# RFMDisplay.net
KiCad netlist of a schematic drawn in EAGLE
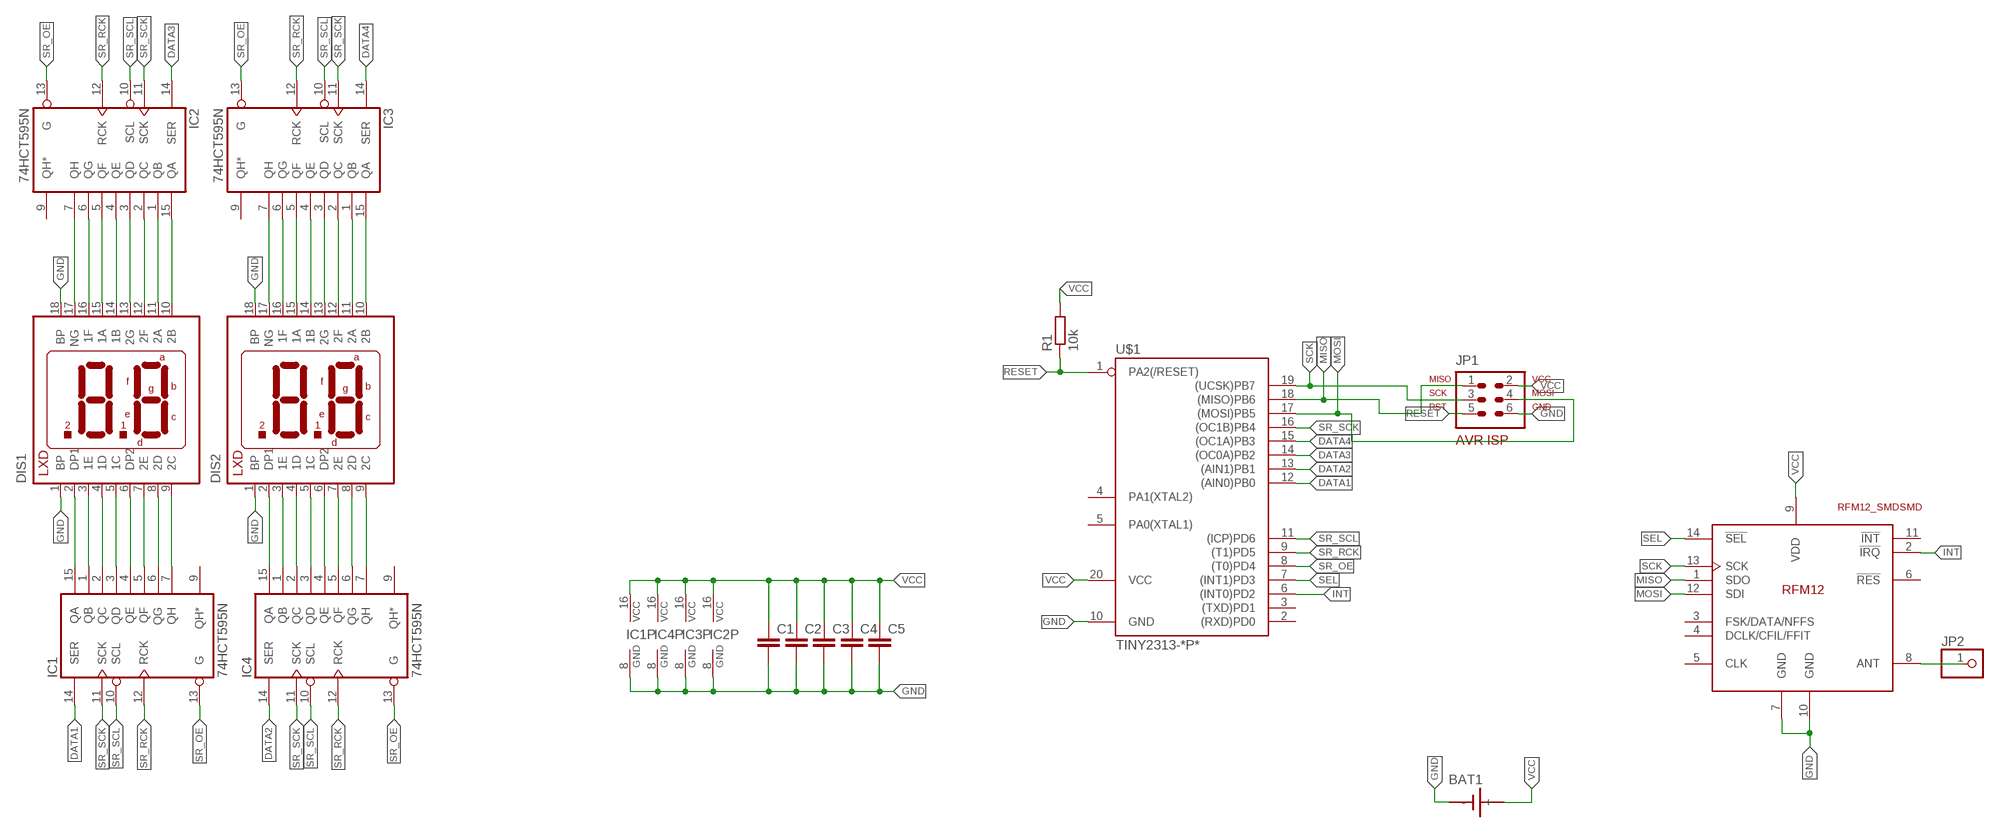
[diagram p0: schematic, sheet 1]

(export (version "E")
  (design (tool "Eeschema 10.0.6"))
  (components
    (comp (ref "BAT1")
      (value "SN2032")
      (footprint "eagle-import:SN2032")
      (libsource (lib "eagle-import") (part "SN2032"))
    )
    (comp (ref "C1")
      (value "C-EUC0805")
      (footprint "eagle-import:C0805")
      (libsource (lib "eagle-import") (part "C-EUC0805"))
    )
    (comp (ref "C2")
      (value "C-EUC0805")
      (footprint "eagle-import:C0805")
      (libsource (lib "eagle-import") (part "C-EUC0805"))
    )
    (comp (ref "C3")
      (value "C-EUC0805")
      (footprint "eagle-import:C0805")
      (libsource (lib "eagle-import") (part "C-EUC0805"))
    )
    (comp (ref "C4")
      (value "C-EUC0805")
      (footprint "eagle-import:C0805")
      (libsource (lib "eagle-import") (part "C-EUC0805"))
    )
    (comp (ref "C5")
      (value "C-EUC0805")
      (footprint "eagle-import:C0805")
      (libsource (lib "eagle-import") (part "C-EUC0805"))
    )
    (comp (ref "DIS1")
      (value "29DIP")
      (footprint "eagle-import:29-D")
      (libsource (lib "eagle-import") (part "29DIP"))
    )
    (comp (ref "DIS2")
      (value "29DIP")
      (footprint "eagle-import:29-D")
      (libsource (lib "eagle-import") (part "29DIP"))
    )
    (comp (ref "IC1")
      (value "74HCT595N")
      (footprint "eagle-import:DIL16")
      (libsource (lib "eagle-import") (part "74595NHCT"))
    )
    (comp (ref "IC2")
      (value "74HCT595N")
      (footprint "eagle-import:DIL16")
      (libsource (lib "eagle-import") (part "74595NHCT"))
    )
    (comp (ref "IC3")
      (value "74HCT595N")
      (footprint "eagle-import:DIL16")
      (libsource (lib "eagle-import") (part "74595NHCT"))
    )
    (comp (ref "IC4")
      (value "74HCT595N")
      (footprint "eagle-import:DIL16")
      (libsource (lib "eagle-import") (part "74595NHCT"))
    )
    (comp (ref "JP1")
      (value "AVR-ISP-6VERT")
      (footprint "eagle-import:AVR-ISP-6")
      (libsource (lib "eagle-import") (part "AVR-ISP-6VERT"))
    )
    (comp (ref "JP2")
      (value "PINHD-1X1")
      (footprint "eagle-import:1X01")
      (libsource (lib "eagle-import") (part "PINHD-1X1"))
    )
    (comp (ref "R1")
      (value "10k")
      (footprint "eagle-import:R1206")
      (libsource (lib "eagle-import") (part "R-EU_R1206"))
    )
    (comp (ref "U$1")
      (value "TINY2313-*P*")
      (footprint "eagle-import:DIL20")
      (libsource (lib "eagle-import") (part "TINY2313-P"))
    )
    (comp (ref "U$2")
      (value "RFM12_SMDSMD")
      (footprint "eagle-import:RFM12")
      (libsource (lib "eagle-import") (part "RFM12_SMDSMD"))
    )
  )
  (nets
    (net (code "1") (name "DATA1") (class "Default")
      (node (ref "IC1") (pin "14") (pinfunction "SER_14") (pintype "input"))
      (node (ref "U$1") (pin "12") (pinfunction "(AIN0)PB0_12") (pintype "bidirectional"))
    )
    (net (code "2") (name "DATA2") (class "Default")
      (node (ref "IC4") (pin "14") (pinfunction "SER_14") (pintype "input"))
      (node (ref "U$1") (pin "13") (pinfunction "(AIN1)PB1_13") (pintype "bidirectional"))
    )
    (net (code "3") (name "DATA3") (class "Default")
      (node (ref "IC2") (pin "14") (pinfunction "SER_14") (pintype "input"))
      (node (ref "U$1") (pin "14") (pinfunction "(OC0A)PB2_14") (pintype "bidirectional"))
    )
    (net (code "4") (name "DATA4") (class "Default")
      (node (ref "IC3") (pin "14") (pinfunction "SER_14") (pintype "input"))
      (node (ref "U$1") (pin "15") (pinfunction "(OC1A)PB3_15") (pintype "bidirectional"))
    )
    (net (code "5") (name "GND") (class "Default")
      (node (ref "BAT1") (pin "-") (pinfunction "-_-") (pintype "passive"))
      (node (ref "C1") (pin "2") (pinfunction "2_2") (pintype "passive"))
      (node (ref "C2") (pin "2") (pinfunction "2_2") (pintype "passive"))
      (node (ref "C3") (pin "2") (pinfunction "2_2") (pintype "passive"))
      (node (ref "C4") (pin "2") (pinfunction "2_2") (pintype "passive"))
      (node (ref "C5") (pin "2") (pinfunction "2_2") (pintype "passive"))
      (node (ref "DIS1") (pin "1") (pinfunction "BP_1") (pintype "passive"))
      (node (ref "DIS1") (pin "18") (pinfunction "BP_18") (pintype "passive"))
      (node (ref "DIS2") (pin "1") (pinfunction "BP_1") (pintype "passive"))
      (node (ref "DIS2") (pin "18") (pinfunction "BP_18") (pintype "passive"))
      (node (ref "IC1") (pin "8") (pinfunction "GND_8") (pintype "power_in"))
      (node (ref "IC2") (pin "8") (pinfunction "GND_8") (pintype "power_in"))
      (node (ref "IC3") (pin "8") (pinfunction "GND_8") (pintype "power_in"))
      (node (ref "IC4") (pin "8") (pinfunction "GND_8") (pintype "power_in"))
      (node (ref "JP1") (pin "6") (pinfunction "6_6") (pintype "passive"))
      (node (ref "U$1") (pin "10") (pinfunction "GND_10") (pintype "power_in"))
      (node (ref "U$2") (pin "10") (pinfunction "GND_10") (pintype "passive"))
      (node (ref "U$2") (pin "7") (pinfunction "GND_7") (pintype "passive"))
    )
    (net (code "6") (name "INT") (class "Default")
      (node (ref "U$1") (pin "6") (pinfunction "(INT0)PD2_6") (pintype "bidirectional"))
      (node (ref "U$2") (pin "2") (pinfunction "~{IRQ}_2") (pintype "output"))
    )
    (net (code "7") (name "MISO") (class "Default")
      (node (ref "JP1") (pin "1") (pinfunction "1_1") (pintype "passive"))
      (node (ref "U$1") (pin "18") (pinfunction "(MISO)PB6_18") (pintype "bidirectional"))
      (node (ref "U$2") (pin "1") (pinfunction "SDO_1") (pintype "output"))
    )
    (net (code "8") (name "MOSI") (class "Default")
      (node (ref "JP1") (pin "4") (pinfunction "4_4") (pintype "passive"))
      (node (ref "U$1") (pin "17") (pinfunction "(MOSI)PB5_17") (pintype "bidirectional"))
      (node (ref "U$2") (pin "12") (pinfunction "SDI_12") (pintype "input"))
    )
    (net (code "9") (name "Net-(DIS1-1A)") (class "Default")
      (node (ref "DIS1") (pin "15") (pinfunction "1A_15") (pintype "passive"))
      (node (ref "IC2") (pin "5") (pinfunction "QF_5") (pintype "tri_state"))
    )
    (net (code "10") (name "Net-(DIS1-1B)") (class "Default")
      (node (ref "DIS1") (pin "14") (pinfunction "1B_14") (pintype "passive"))
      (node (ref "IC2") (pin "4") (pinfunction "QE_4") (pintype "tri_state"))
    )
    (net (code "11") (name "Net-(DIS1-1C)") (class "Default")
      (node (ref "DIS1") (pin "5") (pinfunction "1C_5") (pintype "passive"))
      (node (ref "IC1") (pin "3") (pinfunction "QD_3") (pintype "tri_state"))
    )
    (net (code "12") (name "Net-(DIS1-1D)") (class "Default")
      (node (ref "DIS1") (pin "4") (pinfunction "1D_4") (pintype "passive"))
      (node (ref "IC1") (pin "2") (pinfunction "QC_2") (pintype "tri_state"))
    )
    (net (code "13") (name "Net-(DIS1-1E)") (class "Default")
      (node (ref "DIS1") (pin "3") (pinfunction "1E_3") (pintype "passive"))
      (node (ref "IC1") (pin "1") (pinfunction "QB_1") (pintype "tri_state"))
    )
    (net (code "14") (name "Net-(DIS1-1F)") (class "Default")
      (node (ref "DIS1") (pin "16") (pinfunction "1F_16") (pintype "passive"))
      (node (ref "IC2") (pin "6") (pinfunction "QG_6") (pintype "tri_state"))
    )
    (net (code "15") (name "Net-(DIS1-2A)") (class "Default")
      (node (ref "DIS1") (pin "11") (pinfunction "2A_11") (pintype "passive"))
      (node (ref "IC2") (pin "1") (pinfunction "QB_1") (pintype "tri_state"))
    )
    (net (code "16") (name "Net-(DIS1-2B)") (class "Default")
      (node (ref "DIS1") (pin "10") (pinfunction "2B_10") (pintype "passive"))
      (node (ref "IC2") (pin "15") (pinfunction "QA_15") (pintype "tri_state"))
    )
    (net (code "17") (name "Net-(DIS1-2C)") (class "Default")
      (node (ref "DIS1") (pin "9") (pinfunction "2C_9") (pintype "passive"))
      (node (ref "IC1") (pin "7") (pinfunction "QH_7") (pintype "tri_state"))
    )
    (net (code "18") (name "Net-(DIS1-2D)") (class "Default")
      (node (ref "DIS1") (pin "8") (pinfunction "2D_8") (pintype "passive"))
      (node (ref "IC1") (pin "6") (pinfunction "QG_6") (pintype "tri_state"))
    )
    (net (code "19") (name "Net-(DIS1-2E)") (class "Default")
      (node (ref "DIS1") (pin "7") (pinfunction "2E_7") (pintype "passive"))
      (node (ref "IC1") (pin "5") (pinfunction "QF_5") (pintype "tri_state"))
    )
    (net (code "20") (name "Net-(DIS1-2F)") (class "Default")
      (node (ref "DIS1") (pin "12") (pinfunction "2F_12") (pintype "passive"))
      (node (ref "IC2") (pin "2") (pinfunction "QC_2") (pintype "tri_state"))
    )
    (net (code "21") (name "Net-(DIS1-2G)") (class "Default")
      (node (ref "DIS1") (pin "13") (pinfunction "2G_13") (pintype "passive"))
      (node (ref "IC2") (pin "3") (pinfunction "QD_3") (pintype "tri_state"))
    )
    (net (code "22") (name "Net-(DIS1-DP1)") (class "Default")
      (node (ref "DIS1") (pin "2") (pinfunction "DP1_2") (pintype "passive"))
      (node (ref "IC1") (pin "15") (pinfunction "QA_15") (pintype "tri_state"))
    )
    (net (code "23") (name "Net-(DIS1-DP2)") (class "Default")
      (node (ref "DIS1") (pin "6") (pinfunction "DP2_6") (pintype "passive"))
      (node (ref "IC1") (pin "4") (pinfunction "QE_4") (pintype "tri_state"))
    )
    (net (code "24") (name "Net-(DIS1-NG)") (class "Default")
      (node (ref "DIS1") (pin "17") (pinfunction "NG_17") (pintype "passive"))
      (node (ref "IC2") (pin "7") (pinfunction "QH_7") (pintype "tri_state"))
    )
    (net (code "25") (name "Net-(DIS2-1A)") (class "Default")
      (node (ref "DIS2") (pin "15") (pinfunction "1A_15") (pintype "passive"))
      (node (ref "IC3") (pin "5") (pinfunction "QF_5") (pintype "tri_state"))
    )
    (net (code "26") (name "Net-(DIS2-1B)") (class "Default")
      (node (ref "DIS2") (pin "14") (pinfunction "1B_14") (pintype "passive"))
      (node (ref "IC3") (pin "4") (pinfunction "QE_4") (pintype "tri_state"))
    )
    (net (code "27") (name "Net-(DIS2-1C)") (class "Default")
      (node (ref "DIS2") (pin "5") (pinfunction "1C_5") (pintype "passive"))
      (node (ref "IC4") (pin "3") (pinfunction "QD_3") (pintype "tri_state"))
    )
    (net (code "28") (name "Net-(DIS2-1D)") (class "Default")
      (node (ref "DIS2") (pin "4") (pinfunction "1D_4") (pintype "passive"))
      (node (ref "IC4") (pin "2") (pinfunction "QC_2") (pintype "tri_state"))
    )
    (net (code "29") (name "Net-(DIS2-1E)") (class "Default")
      (node (ref "DIS2") (pin "3") (pinfunction "1E_3") (pintype "passive"))
      (node (ref "IC4") (pin "1") (pinfunction "QB_1") (pintype "tri_state"))
    )
    (net (code "30") (name "Net-(DIS2-1F)") (class "Default")
      (node (ref "DIS2") (pin "16") (pinfunction "1F_16") (pintype "passive"))
      (node (ref "IC3") (pin "6") (pinfunction "QG_6") (pintype "tri_state"))
    )
    (net (code "31") (name "Net-(DIS2-2A)") (class "Default")
      (node (ref "DIS2") (pin "11") (pinfunction "2A_11") (pintype "passive"))
      (node (ref "IC3") (pin "1") (pinfunction "QB_1") (pintype "tri_state"))
    )
    (net (code "32") (name "Net-(DIS2-2B)") (class "Default")
      (node (ref "DIS2") (pin "10") (pinfunction "2B_10") (pintype "passive"))
      (node (ref "IC3") (pin "15") (pinfunction "QA_15") (pintype "tri_state"))
    )
    (net (code "33") (name "Net-(DIS2-2C)") (class "Default")
      (node (ref "DIS2") (pin "9") (pinfunction "2C_9") (pintype "passive"))
      (node (ref "IC4") (pin "7") (pinfunction "QH_7") (pintype "tri_state"))
    )
    (net (code "34") (name "Net-(DIS2-2D)") (class "Default")
      (node (ref "DIS2") (pin "8") (pinfunction "2D_8") (pintype "passive"))
      (node (ref "IC4") (pin "6") (pinfunction "QG_6") (pintype "tri_state"))
    )
    (net (code "35") (name "Net-(DIS2-2E)") (class "Default")
      (node (ref "DIS2") (pin "7") (pinfunction "2E_7") (pintype "passive"))
      (node (ref "IC4") (pin "5") (pinfunction "QF_5") (pintype "tri_state"))
    )
    (net (code "36") (name "Net-(DIS2-2F)") (class "Default")
      (node (ref "DIS2") (pin "12") (pinfunction "2F_12") (pintype "passive"))
      (node (ref "IC3") (pin "2") (pinfunction "QC_2") (pintype "tri_state"))
    )
    (net (code "37") (name "Net-(DIS2-2G)") (class "Default")
      (node (ref "DIS2") (pin "13") (pinfunction "2G_13") (pintype "passive"))
      (node (ref "IC3") (pin "3") (pinfunction "QD_3") (pintype "tri_state"))
    )
    (net (code "38") (name "Net-(DIS2-DP1)") (class "Default")
      (node (ref "DIS2") (pin "2") (pinfunction "DP1_2") (pintype "passive"))
      (node (ref "IC4") (pin "15") (pinfunction "QA_15") (pintype "tri_state"))
    )
    (net (code "39") (name "Net-(DIS2-DP2)") (class "Default")
      (node (ref "DIS2") (pin "6") (pinfunction "DP2_6") (pintype "passive"))
      (node (ref "IC4") (pin "4") (pinfunction "QE_4") (pintype "tri_state"))
    )
    (net (code "40") (name "Net-(DIS2-NG)") (class "Default")
      (node (ref "DIS2") (pin "17") (pinfunction "NG_17") (pintype "passive"))
      (node (ref "IC3") (pin "7") (pinfunction "QH_7") (pintype "tri_state"))
    )
    (net (code "41") (name "Net-(U$2-ANT)") (class "Default")
      (node (ref "JP2") (pin "1") (pinfunction "1_1") (pintype "passive"))
      (node (ref "U$2") (pin "8") (pinfunction "ANT_8") (pintype "bidirectional"))
    )
    (net (code "42") (name "RESET") (class "Default")
      (node (ref "JP1") (pin "5") (pinfunction "5_5") (pintype "passive"))
      (node (ref "R1") (pin "1") (pinfunction "1_1") (pintype "passive"))
      (node (ref "U$1") (pin "1") (pinfunction "PA2(/RESET)_1") (pintype "input"))
    )
    (net (code "43") (name "SCK") (class "Default")
      (node (ref "JP1") (pin "3") (pinfunction "3_3") (pintype "passive"))
      (node (ref "U$1") (pin "19") (pinfunction "(UCSK)PB7_19") (pintype "bidirectional"))
      (node (ref "U$2") (pin "13") (pinfunction "SCK_13") (pintype "input"))
    )
    (net (code "44") (name "SEL") (class "Default")
      (node (ref "U$1") (pin "7") (pinfunction "(INT1)PD3_7") (pintype "bidirectional"))
      (node (ref "U$2") (pin "14") (pinfunction "~{SEL}_14") (pintype "input"))
    )
    (net (code "45") (name "SR_OE") (class "Default")
      (node (ref "IC1") (pin "13") (pinfunction "G_13") (pintype "input"))
      (node (ref "IC2") (pin "13") (pinfunction "G_13") (pintype "input"))
      (node (ref "IC3") (pin "13") (pinfunction "G_13") (pintype "input"))
      (node (ref "IC4") (pin "13") (pinfunction "G_13") (pintype "input"))
      (node (ref "U$1") (pin "8") (pinfunction "(T0)PD4_8") (pintype "bidirectional"))
    )
    (net (code "46") (name "SR_RCK") (class "Default")
      (node (ref "IC1") (pin "12") (pinfunction "RCK_12") (pintype "input"))
      (node (ref "IC2") (pin "12") (pinfunction "RCK_12") (pintype "input"))
      (node (ref "IC3") (pin "12") (pinfunction "RCK_12") (pintype "input"))
      (node (ref "IC4") (pin "12") (pinfunction "RCK_12") (pintype "input"))
      (node (ref "U$1") (pin "9") (pinfunction "(T1)PD5_9") (pintype "bidirectional"))
    )
    (net (code "47") (name "SR_SCK") (class "Default")
      (node (ref "IC1") (pin "11") (pinfunction "SCK_11") (pintype "input"))
      (node (ref "IC2") (pin "11") (pinfunction "SCK_11") (pintype "input"))
      (node (ref "IC3") (pin "11") (pinfunction "SCK_11") (pintype "input"))
      (node (ref "IC4") (pin "11") (pinfunction "SCK_11") (pintype "input"))
      (node (ref "U$1") (pin "16") (pinfunction "(OC1B)PB4_16") (pintype "bidirectional"))
    )
    (net (code "48") (name "SR_SCL") (class "Default")
      (node (ref "IC1") (pin "10") (pinfunction "SCL_10") (pintype "input"))
      (node (ref "IC2") (pin "10") (pinfunction "SCL_10") (pintype "input"))
      (node (ref "IC3") (pin "10") (pinfunction "SCL_10") (pintype "input"))
      (node (ref "IC4") (pin "10") (pinfunction "SCL_10") (pintype "input"))
      (node (ref "U$1") (pin "11") (pinfunction "(ICP)PD6_11") (pintype "bidirectional"))
    )
    (net (code "49") (name "VCC") (class "Default")
      (node (ref "BAT1") (pin "+") (pinfunction "+_+") (pintype "passive"))
      (node (ref "C1") (pin "1") (pinfunction "1_1") (pintype "passive"))
      (node (ref "C2") (pin "1") (pinfunction "1_1") (pintype "passive"))
      (node (ref "C3") (pin "1") (pinfunction "1_1") (pintype "passive"))
      (node (ref "C4") (pin "1") (pinfunction "1_1") (pintype "passive"))
      (node (ref "C5") (pin "1") (pinfunction "1_1") (pintype "passive"))
      (node (ref "IC1") (pin "16") (pinfunction "VCC_16") (pintype "power_in"))
      (node (ref "IC2") (pin "16") (pinfunction "VCC_16") (pintype "power_in"))
      (node (ref "IC3") (pin "16") (pinfunction "VCC_16") (pintype "power_in"))
      (node (ref "IC4") (pin "16") (pinfunction "VCC_16") (pintype "power_in"))
      (node (ref "JP1") (pin "2") (pinfunction "2_2") (pintype "passive"))
      (node (ref "R1") (pin "2") (pinfunction "2_2") (pintype "passive"))
      (node (ref "U$1") (pin "20") (pinfunction "VCC_20") (pintype "power_in"))
      (node (ref "U$2") (pin "9") (pinfunction "VDD_9") (pintype "power_in"))
    )
    (net (code "50") (name "unconnected-(IC1A-QH*-Pad9)") (class "Default")
      (node (ref "IC1") (pin "9") (pinfunction "QH*_9") (pintype "tri_state"))
    )
    (net (code "51") (name "unconnected-(IC2A-QH*-Pad9)") (class "Default")
      (node (ref "IC2") (pin "9") (pinfunction "QH*_9") (pintype "tri_state"))
    )
    (net (code "52") (name "unconnected-(IC3A-QH*-Pad9)") (class "Default")
      (node (ref "IC3") (pin "9") (pinfunction "QH*_9") (pintype "tri_state"))
    )
    (net (code "53") (name "unconnected-(IC4A-QH*-Pad9)") (class "Default")
      (node (ref "IC4") (pin "9") (pinfunction "QH*_9") (pintype "tri_state"))
    )
    (net (code "54") (name "unconnected-(U$1-(RXD)PD0-Pad2)") (class "Default")
      (node (ref "U$1") (pin "2") (pinfunction "(RXD)PD0_2") (pintype "bidirectional"))
    )
    (net (code "55") (name "unconnected-(U$1-(TXD)PD1-Pad3)") (class "Default")
      (node (ref "U$1") (pin "3") (pinfunction "(TXD)PD1_3") (pintype "bidirectional"))
    )
    (net (code "56") (name "unconnected-(U$1-PA0(XTAL1)-Pad5)") (class "Default")
      (node (ref "U$1") (pin "5") (pinfunction "PA0(XTAL1)_5") (pintype "bidirectional"))
    )
    (net (code "57") (name "unconnected-(U$1-PA1(XTAL2)-Pad4)") (class "Default")
      (node (ref "U$1") (pin "4") (pinfunction "PA1(XTAL2)_4") (pintype "bidirectional"))
    )
    (net (code "58") (name "unconnected-(U$2-CLK-Pad5)") (class "Default")
      (node (ref "U$2") (pin "5") (pinfunction "CLK_5") (pintype "output"))
    )
    (net (code "59") (name "unconnected-(U$2-DCLK{slash}CFIL{slash}FFIT-Pad4)") (class "Default")
      (node (ref "U$2") (pin "4") (pinfunction "DCLK/CFIL/FFIT_4") (pintype "bidirectional"))
    )
    (net (code "60") (name "unconnected-(U$2-FSK{slash}DATA{slash}NFFS-Pad3)") (class "Default")
      (node (ref "U$2") (pin "3") (pinfunction "FSK/DATA/NFFS_3") (pintype "bidirectional"))
    )
    (net (code "61") (name "unconnected-(U$2-~{INT}-Pad11)") (class "Default")
      (node (ref "U$2") (pin "11") (pinfunction "~{INT}_11") (pintype "bidirectional"))
    )
    (net (code "62") (name "unconnected-(U$2-~{RES}-Pad6)") (class "Default")
      (node (ref "U$2") (pin "6") (pinfunction "~{RES}_6") (pintype "bidirectional"))
    )
  )
)
